# JTAG_Configuration.net
KiCad netlist of a schematic drawn in Altium Designer
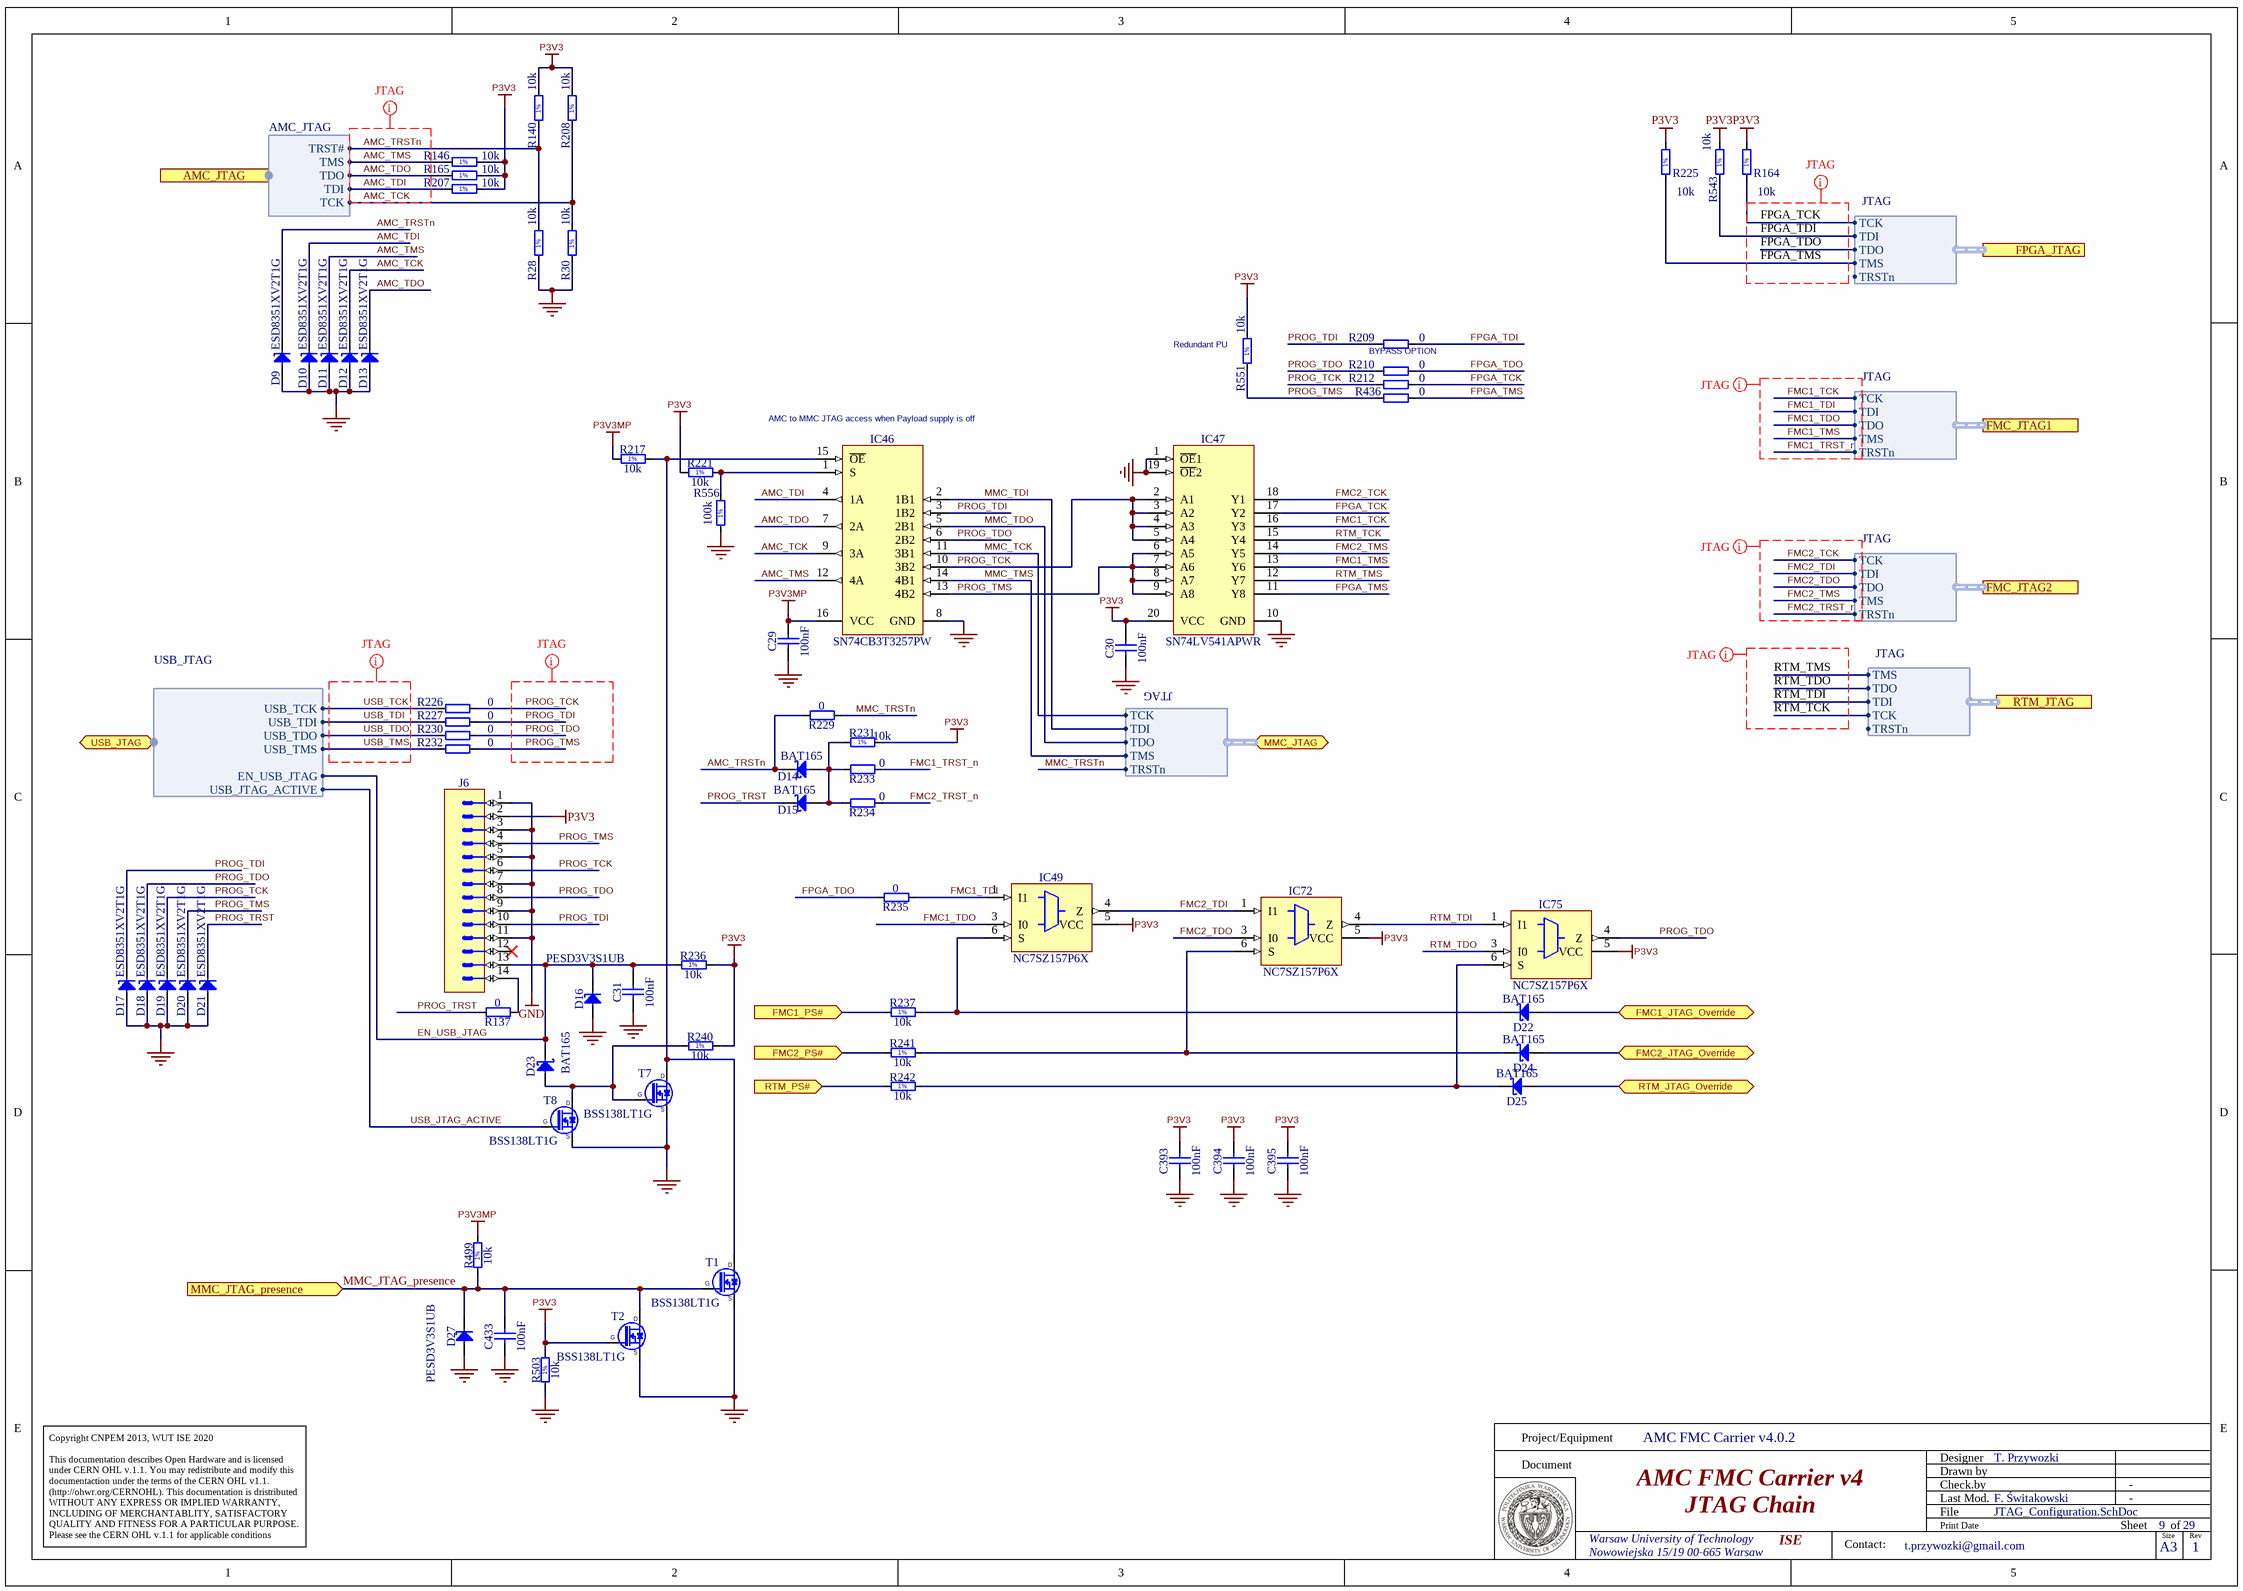
[diagram p0: JTAG_Configuration.SchDoc]

(export (version "E")
  (design (tool "Eeschema 10.0.6"))
  (components
    (comp (ref "C29")
      (value "100nF")
      (footprint "CAPC0603X33N")
      (description "Non-polarised capacitor")
      (fields
        (field (name "MANUFACTURER PART NUMBER") "CC0201_100NF_6.3V_10%_X5R")
        (field (name "MANUFACTURER") "GENERIC")
        (field (name "AUTHOR") "CERN DEM JLC")
      )
      (libsource (lib "Capacitors") (part "Capacitor - non polarized"))
    )
    (comp (ref "C30")
      (value "100nF")
      (footprint "CAPC0603X33N")
      (description "Non-polarised capacitor")
      (fields
        (field (name "MANUFACTURER PART NUMBER") "CC0201_100NF_6.3V_10%_X5R")
        (field (name "MANUFACTURER") "GENERIC")
        (field (name "AUTHOR") "CERN DEM JLC")
      )
      (libsource (lib "Capacitors") (part "Capacitor - non polarized"))
    )
    (comp (ref "C31")
      (value "100nF")
      (footprint "CAPC1005X55N")
      (description "Non-polarised capacitor")
      (fields
        (field (name "MANUFACTURER PART NUMBER") "CC0402_100NF_16V_10%_X5R")
        (field (name "MANUFACTURER") "GENERIC")
        (field (name "AUTHOR") "CERN DEM JLC")
      )
      (libsource (lib "Capacitors") (part "Capacitor - non polarized"))
    )
    (comp (ref "C393")
      (value "100nF")
      (footprint "CAPC0603X33N")
      (description "Non-polarised capacitor")
      (fields
        (field (name "MANUFACTURER PART NUMBER") "CC0201_100NF_6.3V_10%_X5R")
        (field (name "MANUFACTURER") "GENERIC")
        (field (name "AUTHOR") "CERN DEM JLC")
      )
      (libsource (lib "Capacitors") (part "Capacitor - non polarized"))
    )
    (comp (ref "C394")
      (value "100nF")
      (footprint "CAPC0603X33N")
      (description "Non-polarised capacitor")
      (fields
        (field (name "MANUFACTURER PART NUMBER") "CC0201_100NF_6.3V_10%_X5R")
        (field (name "MANUFACTURER") "GENERIC")
        (field (name "AUTHOR") "CERN DEM JLC")
      )
      (libsource (lib "Capacitors") (part "Capacitor - non polarized"))
    )
    (comp (ref "C395")
      (value "100nF")
      (footprint "CAPC0603X33N")
      (description "Non-polarised capacitor")
      (fields
        (field (name "MANUFACTURER PART NUMBER") "CC0201_100NF_6.3V_10%_X5R")
        (field (name "MANUFACTURER") "GENERIC")
        (field (name "AUTHOR") "CERN DEM JLC")
      )
      (libsource (lib "Capacitors") (part "Capacitor - non polarized"))
    )
    (comp (ref "C433")
      (value "100nF")
      (footprint "CAPC1005X55N")
      (description "Non-polarised capacitor")
      (fields
        (field (name "MANUFACTURER PART NUMBER") "CC0402_100NF_16V_10%_X5R")
        (field (name "MANUFACTURER") "GENERIC")
        (field (name "AUTHOR") "CERN DEM JLC")
      )
      (libsource (lib "Capacitors") (part "Capacitor - non polarized"))
    )
    (comp (ref "D9")
      (value "ESD8351XV2T1G")
      (footprint "SODFL1608X65N")
      (description "ESD protection diode")
      (fields
        (field (name "MANUFACTURER") "NXP SEMICONDUCTORS")
        (field (name "VOLTAGE") "3V3")
        (field (name "AUTHOR") "CERN DEM JLC")
      )
      (libsource (lib "ICs And Semiconductors") (part "Diode ESD"))
    )
    (comp (ref "D10")
      (value "ESD8351XV2T1G")
      (footprint "SODFL1608X65N")
      (description "ESD protection diode")
      (fields
        (field (name "MANUFACTURER") "NXP SEMICONDUCTORS")
        (field (name "VOLTAGE") "3V3")
        (field (name "AUTHOR") "CERN DEM JLC")
      )
      (libsource (lib "ICs And Semiconductors") (part "Diode ESD"))
    )
    (comp (ref "D11")
      (value "ESD8351XV2T1G")
      (footprint "SODFL1608X65N")
      (description "ESD protection diode")
      (fields
        (field (name "MANUFACTURER") "NXP SEMICONDUCTORS")
        (field (name "VOLTAGE") "3V3")
        (field (name "AUTHOR") "CERN DEM JLC")
      )
      (libsource (lib "ICs And Semiconductors") (part "Diode ESD"))
    )
    (comp (ref "D12")
      (value "ESD8351XV2T1G")
      (footprint "SODFL1608X65N")
      (description "ESD protection diode")
      (fields
        (field (name "MANUFACTURER") "NXP SEMICONDUCTORS")
        (field (name "VOLTAGE") "3V3")
        (field (name "AUTHOR") "CERN DEM JLC")
      )
      (libsource (lib "ICs And Semiconductors") (part "Diode ESD"))
    )
    (comp (ref "D13")
      (value "ESD8351XV2T1G")
      (footprint "SODFL1608X65N")
      (description "ESD protection diode")
      (fields
        (field (name "MANUFACTURER") "NXP SEMICONDUCTORS")
        (field (name "VOLTAGE") "3V3")
        (field (name "AUTHOR") "CERN DEM JLC")
      )
      (libsource (lib "ICs And Semiconductors") (part "Diode ESD"))
    )
    (comp (ref "D14")
      (value "BAT165")
      (footprint "SOD2512X110N")
      (description "Schottky Diode")
      (fields
        (field (name "MANUFACTURER") "INFINEON")
        (field (name "VOLTAGE") "40V")
        (field (name "AUTHOR") "CERN DEM JLC")
      )
      (libsource (lib "ICs And Semiconductors") (part "Diode Schottky"))
    )
    (comp (ref "D15")
      (value "BAT165")
      (footprint "SOD2512X110N")
      (description "Schottky Diode")
      (fields
        (field (name "MANUFACTURER") "INFINEON")
        (field (name "VOLTAGE") "40V")
        (field (name "AUTHOR") "CERN DEM JLC")
      )
      (libsource (lib "ICs And Semiconductors") (part "Diode Schottky"))
    )
    (comp (ref "D16")
      (value "PESD3V3S1UB")
      (footprint "SODFL1608X65N")
      (description "ESD protection diode")
      (fields
        (field (name "MANUFACTURER") "NXP SEMICONDUCTORS")
        (field (name "VOLTAGE") "3V3")
        (field (name "AUTHOR") "CERN DEM JLC")
      )
      (libsource (lib "ICs And Semiconductors") (part "Diode ESD"))
    )
    (comp (ref "D17")
      (value "ESD8351XV2T1G")
      (footprint "SODFL1608X65N")
      (description "ESD protection diode")
      (fields
        (field (name "MANUFACTURER") "NXP SEMICONDUCTORS")
        (field (name "VOLTAGE") "3V3")
        (field (name "AUTHOR") "CERN DEM JLC")
      )
      (libsource (lib "ICs And Semiconductors") (part "Diode ESD"))
    )
    (comp (ref "D18")
      (value "ESD8351XV2T1G")
      (footprint "SODFL1608X65N")
      (description "ESD protection diode")
      (fields
        (field (name "MANUFACTURER") "NXP SEMICONDUCTORS")
        (field (name "VOLTAGE") "3V3")
        (field (name "AUTHOR") "CERN DEM JLC")
      )
      (libsource (lib "ICs And Semiconductors") (part "Diode ESD"))
    )
    (comp (ref "D19")
      (value "ESD8351XV2T1G")
      (footprint "SODFL1608X65N")
      (description "ESD protection diode")
      (fields
        (field (name "MANUFACTURER") "NXP SEMICONDUCTORS")
        (field (name "VOLTAGE") "3V3")
        (field (name "AUTHOR") "CERN DEM JLC")
      )
      (libsource (lib "ICs And Semiconductors") (part "Diode ESD"))
    )
    (comp (ref "D20")
      (value "ESD8351XV2T1G")
      (footprint "SODFL1608X65N")
      (description "ESD protection diode")
      (fields
        (field (name "MANUFACTURER") "NXP SEMICONDUCTORS")
        (field (name "VOLTAGE") "3V3")
        (field (name "AUTHOR") "CERN DEM JLC")
      )
      (libsource (lib "ICs And Semiconductors") (part "Diode ESD"))
    )
    (comp (ref "D21")
      (value "ESD8351XV2T1G")
      (footprint "SODFL1608X65N")
      (description "ESD protection diode")
      (fields
        (field (name "MANUFACTURER") "NXP SEMICONDUCTORS")
        (field (name "VOLTAGE") "3V3")
        (field (name "AUTHOR") "CERN DEM JLC")
      )
      (libsource (lib "ICs And Semiconductors") (part "Diode ESD"))
    )
    (comp (ref "D22")
      (value "BAT165")
      (footprint "SOD2512X110N")
      (description "Schottky Diode")
      (fields
        (field (name "MANUFACTURER") "INFINEON")
        (field (name "VOLTAGE") "40V")
        (field (name "AUTHOR") "CERN DEM JLC")
      )
      (libsource (lib "ICs And Semiconductors") (part "Diode Schottky"))
    )
    (comp (ref "D23")
      (value "BAT165")
      (footprint "SOD2512X110N")
      (description "Schottky Diode")
      (fields
        (field (name "MANUFACTURER") "INFINEON")
        (field (name "VOLTAGE") "40V")
        (field (name "AUTHOR") "CERN DEM JLC")
      )
      (libsource (lib "ICs And Semiconductors") (part "Diode Schottky"))
    )
    (comp (ref "D24")
      (value "BAT165")
      (footprint "SOD2512X110N")
      (description "Schottky Diode")
      (fields
        (field (name "MANUFACTURER") "INFINEON")
        (field (name "VOLTAGE") "40V")
        (field (name "AUTHOR") "CERN DEM JLC")
      )
      (libsource (lib "ICs And Semiconductors") (part "Diode Schottky"))
    )
    (comp (ref "D25")
      (value "BAT165")
      (footprint "SOD2512X110N")
      (description "Schottky Diode")
      (fields
        (field (name "MANUFACTURER") "INFINEON")
        (field (name "VOLTAGE") "40V")
        (field (name "AUTHOR") "CERN DEM JLC")
      )
      (libsource (lib "ICs And Semiconductors") (part "Diode Schottky"))
    )
    (comp (ref "D27")
      (value "PESD3V3S1UB")
      (footprint "SODFL1608X65N")
      (description "ESD protection diode")
      (fields
        (field (name "MANUFACTURER") "NXP SEMICONDUCTORS")
        (field (name "VOLTAGE") "3V3")
        (field (name "AUTHOR") "CERN DEM JLC")
      )
      (libsource (lib "ICs And Semiconductors") (part "Diode ESD"))
    )
    (comp (ref "IC46")
      (value "SN74CB3T3257PW")
      (footprint "SOP65P640X120-16N")
      (description "4-BIT 1-OF-2 FET Multiplexer/Demultiplexer 2.5V/3.3V Low-Voltage Bus Switch 5V Tolerant Shifter")
      (fields (field (name "MANUFACTURER") "TEXAS INSTRUMENTS") (field (name "AUTHOR") "CERN DEM JLC"))
      (libsource (lib "ICs And Semiconductors") (part "743257"))
    )
    (comp (ref "IC47")
      (value "SN74LV541APWR")
      (footprint "SOP65P640X120-20N")
      (description "Octal Buffer/Line Driver with 3-State Outputs")
      (fields (field (name "MANUFACTURER") "TEXAS INSTRUMENTS") (field (name "AUTHOR") "CERN DEM JLC"))
      (libsource (lib "ICs And Semiconductors") (part "74541"))
    )
    (comp (ref "IC49")
      (value "NC7SZ157P6X")
      (footprint "SOT65P210X110-6N")
      (description "TinyLogic® UHS 2-Input Non-Inverting Multiplexer")
      (fields (field (name "MANUFACTURER") "FAIRCHILD SEMICONDUCTOR") (field (name "AUTHOR") "CERN DEM JLC"))
      (libsource (lib "ICs And Semiconductors") (part "NC7SZ157"))
    )
    (comp (ref "IC72")
      (value "NC7SZ157P6X")
      (footprint "SOT65P210X110-6N")
      (description "TinyLogic® UHS 2-Input Non-Inverting Multiplexer")
      (fields (field (name "MANUFACTURER") "FAIRCHILD SEMICONDUCTOR") (field (name "AUTHOR") "CERN DEM JLC"))
      (libsource (lib "ICs And Semiconductors") (part "NC7SZ157"))
    )
    (comp (ref "IC75")
      (value "NC7SZ157P6X")
      (footprint "SOT65P210X110-6N")
      (description "TinyLogic® UHS 2-Input Non-Inverting Multiplexer")
      (fields (field (name "MANUFACTURER") "FAIRCHILD SEMICONDUCTOR") (field (name "AUTHOR") "CERN DEM JLC"))
      (libsource (lib "ICs And Semiconductors") (part "NC7SZ157"))
    )
    (comp (ref "J6")
      (value "Milli-Grid™")
      (footprint "MOLEX_87832-1420")
      (description "Connector 14 Male")
      (fields
        (field (name "PART NUMBER") "MOLEX_87832-1420")
        (field (name "MANUFACTURER") "MOLEX")
        (field (name "AUTHOR") "CERN DEM JLC")
      )
      (libsource (lib "Connectors") (part "Connector 14 Male"))
    )
    (comp (ref "R28")
      (value "10k")
      (footprint "RESC1005X40N")
      (description "Resistor - 1%")
      (fields
        (field (name "MANUFACTURER PART NUMBER") "R0402_10K_1%_0.0625W_100PPM")
        (field (name "MANUFACTURER") "GENERIC")
        (field (name "AUTHOR") "CERN DEM JLC")
      )
      (libsource (lib "Resistors") (part "Resistor - 1%"))
    )
    (comp (ref "R30")
      (value "10k")
      (footprint "RESC1005X40N")
      (description "Resistor - 1%")
      (fields
        (field (name "MANUFACTURER PART NUMBER") "R0402_10K_1%_0.0625W_100PPM")
        (field (name "MANUFACTURER") "GENERIC")
        (field (name "AUTHOR") "CERN DEM JLC")
      )
      (libsource (lib "Resistors") (part "Resistor - 1%"))
    )
    (comp (ref "R137")
      (value "0")
      (footprint "RESC1005X40N")
      (description "Resistor")
      (fields
        (field (name "MANUFACTURER PART NUMBER") "R0402_0R_JUMPER")
        (field (name "MANUFACTURER") "GENERIC")
        (field (name "AUTHOR") "CERN DEM JLC")
      )
      (libsource (lib "Resistors") (part "Resistor"))
    )
    (comp (ref "R140")
      (value "10k")
      (footprint "RESC1005X40N")
      (description "Resistor - 1%")
      (fields
        (field (name "MANUFACTURER PART NUMBER") "R0402_10K_1%_0.0625W_100PPM")
        (field (name "MANUFACTURER") "GENERIC")
        (field (name "AUTHOR") "CERN DEM JLC")
      )
      (libsource (lib "Resistors") (part "Resistor - 1%"))
    )
    (comp (ref "R146")
      (value "10k")
      (footprint "RESC1005X40N")
      (description "Resistor - 1%")
      (fields
        (field (name "MANUFACTURER PART NUMBER") "R0402_10K_1%_0.0625W_100PPM")
        (field (name "MANUFACTURER") "GENERIC")
        (field (name "AUTHOR") "CERN DEM JLC")
      )
      (libsource (lib "Resistors") (part "Resistor - 1%"))
    )
    (comp (ref "R164")
      (value "10k")
      (footprint "RESC1005X40N")
      (description "Resistor - 1%")
      (fields
        (field (name "PART NUMBER") "R0402_10K_1%_0.0625W_100PPM")
        (field (name "POWER") "0.0625W")
        (field (name "AUTHOR") "CERN DEM JLC")
      )
      (libsource (lib "Resistors") (part "Resistor - 1%"))
    )
    (comp (ref "R165")
      (value "10k")
      (footprint "RESC1005X40N")
      (description "Resistor - 1%")
      (fields
        (field (name "MANUFACTURER PART NUMBER") "R0402_10K_1%_0.0625W_100PPM")
        (field (name "MANUFACTURER") "GENERIC")
        (field (name "AUTHOR") "CERN DEM JLC")
      )
      (libsource (lib "Resistors") (part "Resistor - 1%"))
    )
    (comp (ref "R207")
      (value "10k")
      (footprint "RESC1005X40N")
      (description "Resistor - 1%")
      (fields
        (field (name "MANUFACTURER PART NUMBER") "R0402_10K_1%_0.0625W_100PPM")
        (field (name "MANUFACTURER") "GENERIC")
        (field (name "AUTHOR") "CERN DEM JLC")
      )
      (libsource (lib "Resistors") (part "Resistor - 1%"))
    )
    (comp (ref "R208")
      (value "10k")
      (footprint "RESC1005X40N")
      (description "Resistor - 1%")
      (fields
        (field (name "MANUFACTURER PART NUMBER") "R0402_10K_1%_0.0625W_100PPM")
        (field (name "MANUFACTURER") "GENERIC")
        (field (name "AUTHOR") "CERN DEM JLC")
      )
      (libsource (lib "Resistors") (part "Resistor - 1%"))
    )
    (comp (ref "R209")
      (value "0")
      (footprint "RESC1005X40N")
      (description "Resistor")
      (fields
        (field (name "MANUFACTURER PART NUMBER") "R0402_0R_JUMPER")
        (field (name "MANUFACTURER") "GENERIC")
        (field (name "AUTHOR") "CERN DEM JLC")
      )
      (libsource (lib "Resistors") (part "Resistor"))
    )
    (comp (ref "R210")
      (value "0")
      (footprint "RESC1005X40N")
      (description "Resistor")
      (fields
        (field (name "MANUFACTURER PART NUMBER") "R0402_0R_JUMPER")
        (field (name "MANUFACTURER") "GENERIC")
        (field (name "AUTHOR") "CERN DEM JLC")
      )
      (libsource (lib "Resistors") (part "Resistor"))
    )
    (comp (ref "R212")
      (value "0")
      (footprint "RESC1005X40N")
      (description "Resistor")
      (fields
        (field (name "MANUFACTURER PART NUMBER") "R0402_0R_JUMPER")
        (field (name "MANUFACTURER") "GENERIC")
        (field (name "AUTHOR") "CERN DEM JLC")
      )
      (libsource (lib "Resistors") (part "Resistor"))
    )
    (comp (ref "R217")
      (value "10k")
      (footprint "RESC1005X40N")
      (description "Resistor - 1%")
      (fields
        (field (name "MANUFACTURER PART NUMBER") "R0402_10K_1%_0.0625W_100PPM")
        (field (name "MANUFACTURER") "GENERIC")
        (field (name "AUTHOR") "CERN DEM JLC")
      )
      (libsource (lib "Resistors") (part "Resistor - 1%"))
    )
    (comp (ref "R221")
      (value "10k")
      (footprint "RESC1005X40N")
      (description "Resistor - 1%")
      (fields
        (field (name "MANUFACTURER PART NUMBER") "R0402_10K_1%_0.0625W_100PPM")
        (field (name "MANUFACTURER") "GENERIC")
        (field (name "AUTHOR") "CERN DEM JLC")
      )
      (libsource (lib "Resistors") (part "Resistor - 1%"))
    )
    (comp (ref "R225")
      (value "10k")
      (footprint "RESC1005X40N")
      (description "Resistor - 1%")
      (fields
        (field (name "PART NUMBER") "R0402_10K_1%_0.0625W_100PPM")
        (field (name "POWER") "0.0625W")
        (field (name "AUTHOR") "CERN DEM JLC")
      )
      (libsource (lib "Resistors") (part "Resistor - 1%"))
    )
    (comp (ref "R226")
      (value "0")
      (footprint "RESC1005X40N")
      (description "Resistor")
      (fields
        (field (name "MANUFACTURER PART NUMBER") "R0402_0R_JUMPER")
        (field (name "MANUFACTURER") "GENERIC")
        (field (name "AUTHOR") "CERN DEM JLC")
      )
      (libsource (lib "Resistors") (part "Resistor"))
    )
    (comp (ref "R227")
      (value "0")
      (footprint "RESC1005X40N")
      (description "Resistor")
      (fields
        (field (name "MANUFACTURER PART NUMBER") "R0402_0R_JUMPER")
        (field (name "MANUFACTURER") "GENERIC")
        (field (name "AUTHOR") "CERN DEM JLC")
      )
      (libsource (lib "Resistors") (part "Resistor"))
    )
    (comp (ref "R229")
      (value "0")
      (footprint "RESC1005X40N")
      (description "Resistor")
      (fields
        (field (name "MANUFACTURER PART NUMBER") "R0402_0R_JUMPER")
        (field (name "MANUFACTURER") "GENERIC")
        (field (name "AUTHOR") "CERN DEM JLC")
      )
      (libsource (lib "Resistors") (part "Resistor"))
    )
    (comp (ref "R230")
      (value "0")
      (footprint "RESC1005X40N")
      (description "Resistor")
      (fields
        (field (name "MANUFACTURER PART NUMBER") "R0402_0R_JUMPER")
        (field (name "MANUFACTURER") "GENERIC")
        (field (name "AUTHOR") "CERN DEM JLC")
      )
      (libsource (lib "Resistors") (part "Resistor"))
    )
    (comp (ref "R231")
      (value "10k")
      (footprint "RESC1005X40N")
      (description "Resistor - 1%")
      (fields
        (field (name "MANUFACTURER PART NUMBER") "R0402_10K_1%_0.0625W_100PPM")
        (field (name "MANUFACTURER") "GENERIC")
        (field (name "AUTHOR") "CERN DEM JLC")
      )
      (libsource (lib "Resistors") (part "Resistor - 1%"))
    )
    (comp (ref "R232")
      (value "0")
      (footprint "RESC1005X40N")
      (description "Resistor")
      (fields
        (field (name "MANUFACTURER PART NUMBER") "R0402_0R_JUMPER")
        (field (name "MANUFACTURER") "GENERIC")
        (field (name "AUTHOR") "CERN DEM JLC")
      )
      (libsource (lib "Resistors") (part "Resistor"))
    )
    (comp (ref "R233")
      (value "0")
      (footprint "RESC1005X40N")
      (description "Resistor")
      (fields
        (field (name "MANUFACTURER PART NUMBER") "R0402_0R_JUMPER")
        (field (name "MANUFACTURER") "GENERIC")
        (field (name "AUTHOR") "CERN DEM JLC")
      )
      (libsource (lib "Resistors") (part "Resistor"))
    )
    (comp (ref "R234")
      (value "0")
      (footprint "RESC1005X40N")
      (description "Resistor")
      (fields
        (field (name "MANUFACTURER PART NUMBER") "R0402_0R_JUMPER")
        (field (name "MANUFACTURER") "GENERIC")
        (field (name "AUTHOR") "CERN DEM JLC")
      )
      (libsource (lib "Resistors") (part "Resistor"))
    )
    (comp (ref "R235")
      (value "0")
      (footprint "RESC1005X40N")
      (description "Resistor")
      (fields
        (field (name "MANUFACTURER PART NUMBER") "R0402_0R_JUMPER")
        (field (name "MANUFACTURER") "GENERIC")
        (field (name "AUTHOR") "CERN DEM JLC")
      )
      (libsource (lib "Resistors") (part "Resistor"))
    )
    (comp (ref "R236")
      (value "10k")
      (footprint "RESC1005X40N")
      (description "Resistor - 1%")
      (fields
        (field (name "MANUFACTURER PART NUMBER") "R0402_10K_1%_0.0625W_100PPM")
        (field (name "MANUFACTURER") "GENERIC")
        (field (name "AUTHOR") "CERN DEM JLC")
      )
      (libsource (lib "Resistors") (part "Resistor - 1%"))
    )
    (comp (ref "R237")
      (value "10k")
      (footprint "RESC1005X40N")
      (description "Resistor - 1%")
      (fields
        (field (name "MANUFACTURER PART NUMBER") "R0402_10K_1%_0.0625W_100PPM")
        (field (name "MANUFACTURER") "GENERIC")
        (field (name "AUTHOR") "CERN DEM JLC")
      )
      (libsource (lib "Resistors") (part "Resistor - 1%"))
    )
    (comp (ref "R240")
      (value "10k")
      (footprint "RESC1005X40N")
      (description "Resistor - 1%")
      (fields
        (field (name "MANUFACTURER PART NUMBER") "R0402_10K_1%_0.0625W_100PPM")
        (field (name "MANUFACTURER") "GENERIC")
        (field (name "AUTHOR") "CERN DEM JLC")
      )
      (libsource (lib "Resistors") (part "Resistor - 1%"))
    )
    (comp (ref "R241")
      (value "10k")
      (footprint "RESC1005X40N")
      (description "Resistor - 1%")
      (fields
        (field (name "MANUFACTURER PART NUMBER") "R0402_10K_1%_0.0625W_100PPM")
        (field (name "MANUFACTURER") "GENERIC")
        (field (name "AUTHOR") "CERN DEM JLC")
      )
      (libsource (lib "Resistors") (part "Resistor - 1%"))
    )
    (comp (ref "R242")
      (value "10k")
      (footprint "RESC1005X40N")
      (description "Resistor - 1%")
      (fields
        (field (name "MANUFACTURER PART NUMBER") "R0402_10K_1%_0.0625W_100PPM")
        (field (name "MANUFACTURER") "GENERIC")
        (field (name "AUTHOR") "CERN DEM JLC")
      )
      (libsource (lib "Resistors") (part "Resistor - 1%"))
    )
    (comp (ref "R436")
      (value "0")
      (footprint "RESC1005X40N")
      (description "Resistor")
      (fields
        (field (name "MANUFACTURER PART NUMBER") "R0402_0R_JUMPER")
        (field (name "MANUFACTURER") "GENERIC")
        (field (name "AUTHOR") "CERN DEM JLC")
      )
      (libsource (lib "Resistors") (part "Resistor"))
    )
    (comp (ref "R499")
      (value "10k")
      (footprint "RESC1005X40N")
      (description "Resistor - 1%")
      (fields
        (field (name "MANUFACTURER PART NUMBER") "R0402_10K_1%_0.0625W_100PPM")
        (field (name "MANUFACTURER") "GENERIC")
        (field (name "AUTHOR") "CERN DEM JLC")
      )
      (libsource (lib "Resistors") (part "Resistor - 1%"))
    )
    (comp (ref "R503")
      (value "10k")
      (footprint "RESC1005X40N")
      (description "Resistor - 1%")
      (fields
        (field (name "MANUFACTURER PART NUMBER") "R0402_10K_1%_0.0625W_100PPM")
        (field (name "MANUFACTURER") "GENERIC")
        (field (name "AUTHOR") "CERN DEM JLC")
      )
      (libsource (lib "Resistors") (part "Resistor - 1%"))
    )
    (comp (ref "R543")
      (value "10k")
      (footprint "RESC1005X40N")
      (description "Resistor - 1%")
      (fields
        (field (name "MANUFACTURER PART NUMBER") "R0402_10K_1%_0.0625W_100PPM")
        (field (name "MANUFACTURER") "GENERIC")
        (field (name "AUTHOR") "CERN DEM JLC")
      )
      (libsource (lib "Resistors") (part "Resistor - 1%"))
    )
    (comp (ref "R551")
      (value "10k")
      (footprint "RESC1005X40N")
      (description "Resistor - 1%")
      (fields
        (field (name "MANUFACTURER PART NUMBER") "R0402_10K_1%_0.0625W_100PPM")
        (field (name "MANUFACTURER") "GENERIC")
        (field (name "AUTHOR") "CERN DEM JLC")
      )
      (libsource (lib "Resistors") (part "Resistor - 1%"))
    )
    (comp (ref "R556")
      (value "100k")
      (footprint "RESC1005X40N")
      (description "Resistor - 1%")
      (fields
        (field (name "PART NUMBER") "R0402_100K_1%_0.0625W_100PPM")
        (field (name "POWER") "0.0625W")
        (field (name "AUTHOR") "CERN DEM JLC")
      )
      (libsource (lib "Resistors") (part "Resistor - 1%"))
    )
    (comp (ref "T1")
      (value "BSS138LT1G")
      (footprint "SOT95P240X110-3N")
      (description "N-CHANNEL MOSFET WITH DIODE")
      (fields (field (name "MANUFACTURER") "ON SEMICONDUCTOR") (field (name "AUTHOR") "CERN DEM JLC"))
      (libsource (lib "ICs And Semiconductors") (part "N-MOSFET-D 1G 2S 3D"))
    )
    (comp (ref "T2")
      (value "BSS138LT1G")
      (footprint "SOT95P240X110-3N")
      (description "N-CHANNEL MOSFET WITH DIODE")
      (fields (field (name "MANUFACTURER") "ON SEMICONDUCTOR") (field (name "AUTHOR") "CERN DEM JLC"))
      (libsource (lib "ICs And Semiconductors") (part "N-MOSFET-D 1G 2S 3D"))
    )
    (comp (ref "T7")
      (value "BSS138LT1G")
      (footprint "SOT95P240X110-3N")
      (description "N-CHANNEL MOSFET WITH DIODE")
      (fields (field (name "MANUFACTURER") "ON SEMICONDUCTOR") (field (name "AUTHOR") "CERN DEM JLC"))
      (libsource (lib "ICs And Semiconductors") (part "N-MOSFET-D 1G 2S 3D"))
    )
    (comp (ref "T8")
      (value "BSS138LT1G")
      (footprint "SOT95P240X110-3N")
      (description "N-CHANNEL MOSFET WITH DIODE")
      (fields (field (name "MANUFACTURER") "ON SEMICONDUCTOR") (field (name "AUTHOR") "CERN DEM JLC"))
      (libsource (lib "ICs And Semiconductors") (part "N-MOSFET-D 1G 2S 3D"))
    )
  )
  (nets
    (net (code "4") (name "/AMC_TCK") (class "Default")
      (node (ref "D12") (pin "1") (pinfunction "C_1") (pintype "passive"))
      (node (ref "IC46") (pin "9") (pinfunction "3A_9") (pintype "output"))
      (node (ref "R208") (pin "2") (pinfunction "2_2") (pintype "passive"))
      (node (ref "R30") (pin "1") (pinfunction "1_1") (pintype "passive"))
    )
    (net (code "5") (name "/AMC_TDI") (class "Default")
      (node (ref "D10") (pin "1") (pinfunction "C_1") (pintype "passive"))
      (node (ref "IC46") (pin "4") (pinfunction "1A_4") (pintype "output"))
      (node (ref "R207") (pin "2") (pinfunction "2_2") (pintype "passive"))
    )
    (net (code "6") (name "/AMC_TDO") (class "Default")
      (node (ref "D13") (pin "1") (pinfunction "C_1") (pintype "passive"))
      (node (ref "IC46") (pin "7") (pinfunction "2A_7") (pintype "output"))
      (node (ref "R165") (pin "2") (pinfunction "2_2") (pintype "passive"))
    )
    (net (code "7") (name "/AMC_TMS") (class "Default")
      (node (ref "D11") (pin "1") (pinfunction "C_1") (pintype "passive"))
      (node (ref "IC46") (pin "12") (pinfunction "4A_12") (pintype "output"))
      (node (ref "R146") (pin "2") (pinfunction "2_2") (pintype "passive"))
    )
    (net (code "8") (name "/AMC_TRSTn") (class "Default")
      (node (ref "D14") (pin "1") (pinfunction "C_1") (pintype "passive"))
      (node (ref "D9") (pin "1") (pinfunction "C_1") (pintype "passive"))
      (node (ref "R140") (pin "2") (pinfunction "2_2") (pintype "passive"))
      (node (ref "R229") (pin "2") (pinfunction "2_2") (pintype "passive"))
      (node (ref "R28") (pin "1") (pinfunction "1_1") (pintype "passive"))
    )
    (net (code "9") (name "/EN_USB_JTAG") (class "Default")
      (node (ref "C31") (pin "2") (pinfunction "2_2") (pintype "passive"))
      (node (ref "D16") (pin "1") (pinfunction "C_1") (pintype "passive"))
      (node (ref "D23") (pin "1") (pinfunction "C_1") (pintype "passive"))
      (node (ref "J6") (pin "13") (pinfunction "13_13") (pintype "bidirectional"))
      (node (ref "R236") (pin "1") (pinfunction "1_1") (pintype "passive"))
    )
    (net (code "10") (name "/FMC1_JTAG_Override") (class "Default")
      (node (ref "D22") (pin "2") (pinfunction "A_2") (pintype "passive"))
    )
    (net (code "11") (name "/FMC1_PS#") (class "Default")
      (node (ref "R237") (pin "2") (pinfunction "2_2") (pintype "passive"))
    )
    (net (code "12") (name "/FMC1_TCK") (class "Default")
      (node (ref "IC47") (pin "16") (pinfunction "Y3_16") (pintype "tri_state"))
    )
    (net (code "13") (name "/FMC1_TDI") (class "Default")
      (node (ref "IC49") (pin "1") (pinfunction "I1_1") (pintype "input"))
      (node (ref "R235") (pin "1") (pinfunction "1_1") (pintype "passive"))
    )
    (net (code "14") (name "/FMC1_TDO") (class "Default")
      (node (ref "IC49") (pin "3") (pinfunction "I0_3") (pintype "input"))
    )
    (net (code "15") (name "/FMC1_TMS") (class "Default")
      (node (ref "IC47") (pin "13") (pinfunction "Y6_13") (pintype "tri_state"))
    )
    (net (code "16") (name "/FMC1_TRST_n") (class "Default")
      (node (ref "R233") (pin "1") (pinfunction "1_1") (pintype "passive"))
    )
    (net (code "17") (name "/FMC2_JTAG_Override") (class "Default")
      (node (ref "D24") (pin "2") (pinfunction "A_2") (pintype "passive"))
    )
    (net (code "18") (name "/FMC2_PS#") (class "Default")
      (node (ref "R241") (pin "2") (pinfunction "2_2") (pintype "passive"))
    )
    (net (code "19") (name "/FMC2_TCK") (class "Default")
      (node (ref "IC47") (pin "18") (pinfunction "Y1_18") (pintype "tri_state"))
    )
    (net (code "20") (name "/FMC2_TDI") (class "Default")
      (node (ref "IC49") (pin "4") (pinfunction "Z_4") (pintype "output"))
      (node (ref "IC72") (pin "1") (pinfunction "I1_1") (pintype "input"))
    )
    (net (code "21") (name "/FMC2_TDO") (class "Default")
      (node (ref "IC72") (pin "3") (pinfunction "I0_3") (pintype "input"))
    )
    (net (code "22") (name "/FMC2_TMS") (class "Default")
      (node (ref "IC47") (pin "14") (pinfunction "Y5_14") (pintype "tri_state"))
    )
    (net (code "23") (name "/FMC2_TRST_n") (class "Default")
      (node (ref "R234") (pin "1") (pinfunction "1_1") (pintype "passive"))
    )
    (net (code "24") (name "/FPGA_TCK") (class "Default")
      (node (ref "IC47") (pin "17") (pinfunction "Y2_17") (pintype "tri_state"))
      (node (ref "R164") (pin "1") (pinfunction "1_1") (pintype "passive"))
      (node (ref "R212") (pin "1") (pinfunction "1_1") (pintype "passive"))
    )
    (net (code "25") (name "/FPGA_TDI") (class "Default")
      (node (ref "R209") (pin "1") (pinfunction "1_1") (pintype "passive"))
      (node (ref "R543") (pin "2") (pinfunction "2_2") (pintype "passive"))
    )
    (net (code "26") (name "/FPGA_TDO") (class "Default")
      (node (ref "R210") (pin "1") (pinfunction "1_1") (pintype "passive"))
      (node (ref "R235") (pin "2") (pinfunction "2_2") (pintype "passive"))
    )
    (net (code "27") (name "/FPGA_TMS") (class "Default")
      (node (ref "IC47") (pin "11") (pinfunction "Y8_11") (pintype "tri_state"))
      (node (ref "R225") (pin "1") (pinfunction "1_1") (pintype "passive"))
      (node (ref "R436") (pin "1") (pinfunction "1_1") (pintype "passive"))
    )
    (net (code "28") (name "/MMC_JTAG_presence") (class "Default")
      (node (ref "C433") (pin "2") (pinfunction "2_2") (pintype "passive"))
      (node (ref "D27") (pin "1") (pinfunction "C_1") (pintype "passive"))
      (node (ref "R499") (pin "1") (pinfunction "1_1") (pintype "passive"))
      (node (ref "T1") (pin "1") (pinfunction "G_1") (pintype "passive"))
      (node (ref "T2") (pin "3") (pinfunction "D_3") (pintype "passive"))
    )
    (net (code "29") (name "/MMC_TCK") (class "Default")
      (node (ref "IC46") (pin "11") (pinfunction "3B1_11") (pintype "input"))
    )
    (net (code "30") (name "/MMC_TDI") (class "Default")
      (node (ref "IC46") (pin "2") (pinfunction "1B1_2") (pintype "input"))
    )
    (net (code "31") (name "/MMC_TDO") (class "Default")
      (node (ref "IC46") (pin "5") (pinfunction "2B1_5") (pintype "input"))
    )
    (net (code "32") (name "/MMC_TMS") (class "Default")
      (node (ref "IC46") (pin "14") (pinfunction "4B1_14") (pintype "input"))
    )
    (net (code "33") (name "/MMC_TRSTn") (class "Default")
      (node (ref "R229") (pin "1") (pinfunction "1_1") (pintype "passive"))
    )
    (net (code "34") (name "/PROG_TCK") (class "Default")
      (node (ref "D19") (pin "1") (pinfunction "C_1") (pintype "passive"))
      (node (ref "IC46") (pin "10") (pinfunction "3B2_10") (pintype "input"))
      (node (ref "IC47") (pin "2") (pinfunction "A1_2") (pintype "input"))
      (node (ref "IC47") (pin "3") (pinfunction "A2_3") (pintype "input"))
      (node (ref "IC47") (pin "4") (pinfunction "A3_4") (pintype "input"))
      (node (ref "IC47") (pin "5") (pinfunction "A4_5") (pintype "input"))
      (node (ref "J6") (pin "6") (pinfunction "6_6") (pintype "bidirectional"))
      (node (ref "R212") (pin "2") (pinfunction "2_2") (pintype "passive"))
      (node (ref "R226") (pin "1") (pinfunction "1_1") (pintype "passive"))
    )
    (net (code "35") (name "/PROG_TDI") (class "Default")
      (node (ref "D17") (pin "1") (pinfunction "C_1") (pintype "passive"))
      (node (ref "IC46") (pin "3") (pinfunction "1B2_3") (pintype "input"))
      (node (ref "J6") (pin "10") (pinfunction "10_10") (pintype "bidirectional"))
      (node (ref "R209") (pin "2") (pinfunction "2_2") (pintype "passive"))
      (node (ref "R227") (pin "1") (pinfunction "1_1") (pintype "passive"))
    )
    (net (code "36") (name "/PROG_TDO") (class "Default")
      (node (ref "D18") (pin "1") (pinfunction "C_1") (pintype "passive"))
      (node (ref "IC46") (pin "6") (pinfunction "2B2_6") (pintype "input"))
      (node (ref "IC75") (pin "4") (pinfunction "Z_4") (pintype "output"))
      (node (ref "J6") (pin "8") (pinfunction "8_8") (pintype "bidirectional"))
      (node (ref "R210") (pin "2") (pinfunction "2_2") (pintype "passive"))
      (node (ref "R230") (pin "1") (pinfunction "1_1") (pintype "passive"))
    )
    (net (code "37") (name "/PROG_TMS") (class "Default")
      (node (ref "D20") (pin "1") (pinfunction "C_1") (pintype "passive"))
      (node (ref "IC46") (pin "13") (pinfunction "4B2_13") (pintype "input"))
      (node (ref "IC47") (pin "6") (pinfunction "A5_6") (pintype "input"))
      (node (ref "IC47") (pin "7") (pinfunction "A6_7") (pintype "input"))
      (node (ref "IC47") (pin "8") (pinfunction "A7_8") (pintype "input"))
      (node (ref "IC47") (pin "9") (pinfunction "A8_9") (pintype "input"))
      (node (ref "J6") (pin "4") (pinfunction "4_4") (pintype "bidirectional"))
      (node (ref "R232") (pin "1") (pinfunction "1_1") (pintype "passive"))
      (node (ref "R436") (pin "2") (pinfunction "2_2") (pintype "passive"))
      (node (ref "R551") (pin "2") (pinfunction "2_2") (pintype "passive"))
    )
    (net (code "38") (name "/PROG_TRST") (class "Default")
      (node (ref "D15") (pin "1") (pinfunction "C_1") (pintype "passive"))
      (node (ref "D21") (pin "1") (pinfunction "C_1") (pintype "passive"))
      (node (ref "R137") (pin "2") (pinfunction "2_2") (pintype "passive"))
    )
    (net (code "39") (name "/RTM_JTAG_Override") (class "Default")
      (node (ref "D25") (pin "2") (pinfunction "A_2") (pintype "passive"))
    )
    (net (code "40") (name "/RTM_PS#") (class "Default")
      (node (ref "R242") (pin "2") (pinfunction "2_2") (pintype "passive"))
    )
    (net (code "41") (name "/RTM_TCK") (class "Default")
      (node (ref "IC47") (pin "15") (pinfunction "Y4_15") (pintype "tri_state"))
    )
    (net (code "42") (name "/RTM_TDI") (class "Default")
      (node (ref "IC72") (pin "4") (pinfunction "Z_4") (pintype "output"))
      (node (ref "IC75") (pin "1") (pinfunction "I1_1") (pintype "input"))
    )
    (net (code "43") (name "/RTM_TDO") (class "Default")
      (node (ref "IC75") (pin "3") (pinfunction "I0_3") (pintype "input"))
    )
    (net (code "44") (name "/RTM_TMS") (class "Default")
      (node (ref "IC47") (pin "12") (pinfunction "Y7_12") (pintype "tri_state"))
    )
    (net (code "45") (name "/USB_JTAG_ACTIVE") (class "Default")
      (node (ref "T8") (pin "1") (pinfunction "G_1") (pintype "passive"))
    )
    (net (code "46") (name "/USB_TCK") (class "Default")
      (node (ref "R226") (pin "2") (pinfunction "2_2") (pintype "passive"))
    )
    (net (code "47") (name "/USB_TDI") (class "Default")
      (node (ref "R227") (pin "2") (pinfunction "2_2") (pintype "passive"))
    )
    (net (code "48") (name "/USB_TDO") (class "Default")
      (node (ref "R230") (pin "2") (pinfunction "2_2") (pintype "passive"))
    )
    (net (code "49") (name "/USB_TMS") (class "Default")
      (node (ref "R232") (pin "2") (pinfunction "2_2") (pintype "passive"))
    )
    (net (code "53") (name "GND") (class "Default")
      (node (ref "C29") (pin "1") (pinfunction "1_1") (pintype "passive"))
      (node (ref "C30") (pin "1") (pinfunction "1_1") (pintype "passive"))
      (node (ref "C31") (pin "1") (pinfunction "1_1") (pintype "passive"))
      (node (ref "C393") (pin "1") (pinfunction "1_1") (pintype "passive"))
      (node (ref "C394") (pin "1") (pinfunction "1_1") (pintype "passive"))
      (node (ref "C395") (pin "1") (pinfunction "1_1") (pintype "passive"))
      (node (ref "C433") (pin "1") (pinfunction "1_1") (pintype "passive"))
      (node (ref "D10") (pin "2") (pinfunction "A_2") (pintype "passive"))
      (node (ref "D11") (pin "2") (pinfunction "A_2") (pintype "passive"))
      (node (ref "D12") (pin "2") (pinfunction "A_2") (pintype "passive"))
      (node (ref "D13") (pin "2") (pinfunction "A_2") (pintype "passive"))
      (node (ref "D16") (pin "2") (pinfunction "A_2") (pintype "passive"))
      (node (ref "D17") (pin "2") (pinfunction "A_2") (pintype "passive"))
      (node (ref "D18") (pin "2") (pinfunction "A_2") (pintype "passive"))
      (node (ref "D19") (pin "2") (pinfunction "A_2") (pintype "passive"))
      (node (ref "D20") (pin "2") (pinfunction "A_2") (pintype "passive"))
      (node (ref "D21") (pin "2") (pinfunction "A_2") (pintype "passive"))
      (node (ref "D27") (pin "2") (pinfunction "A_2") (pintype "passive"))
      (node (ref "D9") (pin "2") (pinfunction "A_2") (pintype "passive"))
      (node (ref "IC46") (pin "8") (pinfunction "GND_8") (pintype "power_in"))
      (node (ref "IC47") (pin "1") (pinfunction "~{OE}1_1") (pintype "input"))
      (node (ref "IC47") (pin "10") (pinfunction "GND_10") (pintype "power_in"))
      (node (ref "IC47") (pin "19") (pinfunction "~{OE}2_19") (pintype "input"))
      (node (ref "IC49") (pin "2") (pinfunction "GND_2") (pintype "power_in"))
      (node (ref "IC72") (pin "2") (pinfunction "GND_2") (pintype "power_in"))
      (node (ref "IC75") (pin "2") (pinfunction "GND_2") (pintype "power_in"))
      (node (ref "J6") (pin "1") (pinfunction "1_1") (pintype "bidirectional"))
      (node (ref "J6") (pin "11") (pinfunction "11_11") (pintype "bidirectional"))
      (node (ref "J6") (pin "3") (pinfunction "3_3") (pintype "bidirectional"))
      (node (ref "J6") (pin "5") (pinfunction "5_5") (pintype "bidirectional"))
      (node (ref "J6") (pin "7") (pinfunction "7_7") (pintype "bidirectional"))
      (node (ref "J6") (pin "9") (pinfunction "9_9") (pintype "bidirectional"))
      (node (ref "R28") (pin "2") (pinfunction "2_2") (pintype "passive"))
      (node (ref "R30") (pin "2") (pinfunction "2_2") (pintype "passive"))
      (node (ref "R503") (pin "1") (pinfunction "1_1") (pintype "passive"))
      (node (ref "R556") (pin "1") (pinfunction "1_1") (pintype "passive"))
      (node (ref "T1") (pin "2") (pinfunction "S_2") (pintype "passive"))
      (node (ref "T2") (pin "2") (pinfunction "S_2") (pintype "passive"))
      (node (ref "T7") (pin "2") (pinfunction "S_2") (pintype "passive"))
      (node (ref "T8") (pin "2") (pinfunction "S_2") (pintype "passive"))
    )
    (net (code "54") (name "Net-(D14-A)") (class "Default")
      (node (ref "D14") (pin "2") (pinfunction "A_2") (pintype "passive"))
      (node (ref "D15") (pin "2") (pinfunction "A_2") (pintype "passive"))
      (node (ref "R231") (pin "2") (pinfunction "2_2") (pintype "passive"))
      (node (ref "R233") (pin "2") (pinfunction "2_2") (pintype "passive"))
      (node (ref "R234") (pin "2") (pinfunction "2_2") (pintype "passive"))
    )
    (net (code "55") (name "Net-(D22-C)") (class "Default")
      (node (ref "D22") (pin "1") (pinfunction "C_1") (pintype "passive"))
      (node (ref "IC49") (pin "6") (pinfunction "S_6") (pintype "input"))
      (node (ref "R237") (pin "1") (pinfunction "1_1") (pintype "passive"))
    )
    (net (code "56") (name "Net-(D23-A)") (class "Default")
      (node (ref "D23") (pin "2") (pinfunction "A_2") (pintype "passive"))
      (node (ref "R240") (pin "1") (pinfunction "1_1") (pintype "passive"))
      (node (ref "T7") (pin "1") (pinfunction "G_1") (pintype "passive"))
      (node (ref "T8") (pin "3") (pinfunction "D_3") (pintype "passive"))
    )
    (net (code "57") (name "Net-(D24-C)") (class "Default")
      (node (ref "D24") (pin "1") (pinfunction "C_1") (pintype "passive"))
      (node (ref "IC72") (pin "6") (pinfunction "S_6") (pintype "input"))
      (node (ref "R241") (pin "1") (pinfunction "1_1") (pintype "passive"))
    )
    (net (code "58") (name "Net-(D25-C)") (class "Default")
      (node (ref "D25") (pin "1") (pinfunction "C_1") (pintype "passive"))
      (node (ref "IC75") (pin "6") (pinfunction "S_6") (pintype "input"))
      (node (ref "R242") (pin "1") (pinfunction "1_1") (pintype "passive"))
    )
    (net (code "59") (name "Net-(IC46-S)") (class "Default")
      (node (ref "IC46") (pin "1") (pinfunction "S_1") (pintype "input"))
      (node (ref "R221") (pin "1") (pinfunction "1_1") (pintype "passive"))
      (node (ref "R556") (pin "2") (pinfunction "2_2") (pintype "passive"))
    )
    (net (code "60") (name "Net-(IC46-~{OE})") (class "Default")
      (node (ref "IC46") (pin "15") (pinfunction "~{OE}_15") (pintype "input"))
      (node (ref "R217") (pin "1") (pinfunction "1_1") (pintype "passive"))
      (node (ref "T1") (pin "3") (pinfunction "D_3") (pintype "passive"))
      (node (ref "T7") (pin "3") (pinfunction "D_3") (pintype "passive"))
    )
    (net (code "61") (name "Net-(J6-Pad14)") (class "Default")
      (node (ref "J6") (pin "14") (pinfunction "14_14") (pintype "bidirectional"))
      (node (ref "R137") (pin "1") (pinfunction "1_1") (pintype "passive"))
    )
    (net (code "62") (name "P3V3") (class "Default")
      (node (ref "C30") (pin "2") (pinfunction "2_2") (pintype "passive"))
      (node (ref "C393") (pin "2") (pinfunction "2_2") (pintype "passive"))
      (node (ref "C394") (pin "2") (pinfunction "2_2") (pintype "passive"))
      (node (ref "C395") (pin "2") (pinfunction "2_2") (pintype "passive"))
      (node (ref "IC47") (pin "20") (pinfunction "VCC_20") (pintype "power_in"))
      (node (ref "IC49") (pin "5") (pinfunction "VCC_5") (pintype "power_in"))
      (node (ref "IC72") (pin "5") (pinfunction "VCC_5") (pintype "power_in"))
      (node (ref "IC75") (pin "5") (pinfunction "VCC_5") (pintype "power_in"))
      (node (ref "J6") (pin "2") (pinfunction "2_2") (pintype "bidirectional"))
      (node (ref "R140") (pin "1") (pinfunction "1_1") (pintype "passive"))
      (node (ref "R146") (pin "1") (pinfunction "1_1") (pintype "passive"))
      (node (ref "R164") (pin "2") (pinfunction "2_2") (pintype "passive"))
      (node (ref "R165") (pin "1") (pinfunction "1_1") (pintype "passive"))
      (node (ref "R207") (pin "1") (pinfunction "1_1") (pintype "passive"))
      (node (ref "R208") (pin "1") (pinfunction "1_1") (pintype "passive"))
      (node (ref "R221") (pin "2") (pinfunction "2_2") (pintype "passive"))
      (node (ref "R225") (pin "2") (pinfunction "2_2") (pintype "passive"))
      (node (ref "R231") (pin "1") (pinfunction "1_1") (pintype "passive"))
      (node (ref "R236") (pin "2") (pinfunction "2_2") (pintype "passive"))
      (node (ref "R240") (pin "2") (pinfunction "2_2") (pintype "passive"))
      (node (ref "R503") (pin "2") (pinfunction "2_2") (pintype "passive"))
      (node (ref "R543") (pin "1") (pinfunction "1_1") (pintype "passive"))
      (node (ref "R551") (pin "1") (pinfunction "1_1") (pintype "passive"))
      (node (ref "T2") (pin "1") (pinfunction "G_1") (pintype "passive"))
    )
    (net (code "63") (name "P3V3MP") (class "Default")
      (node (ref "C29") (pin "2") (pinfunction "2_2") (pintype "passive"))
      (node (ref "IC46") (pin "16") (pinfunction "VCC_16") (pintype "power_in"))
      (node (ref "R217") (pin "2") (pinfunction "2_2") (pintype "passive"))
      (node (ref "R499") (pin "2") (pinfunction "2_2") (pintype "passive"))
    )
    (net (code "64") (name "unconnected-(J6-Pad12)") (class "Default")
      (node (ref "J6") (pin "12") (pinfunction "12_12") (pintype "bidirectional+no_connect"))
    )
  )
)
